# Temperature_and_Altitude.net
KiCad netlist of a schematic drawn in Altium Designer
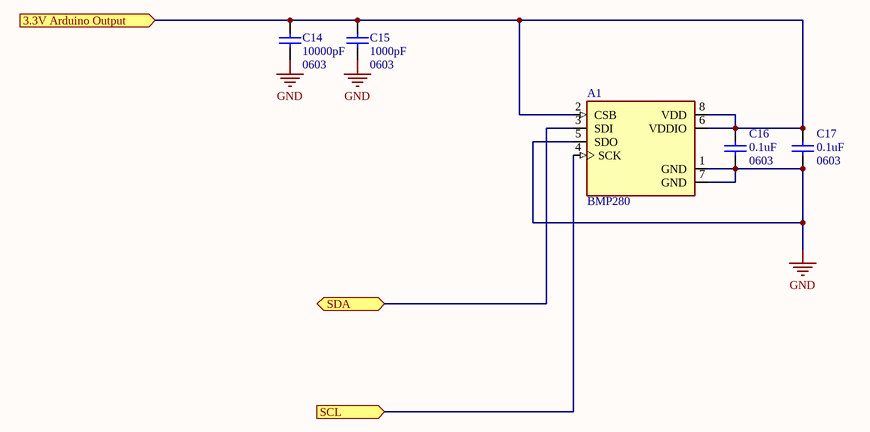
[diagram p0: Temperature and Altitude.SchDoc]

(export (version "E")
  (design (tool "Eeschema 10.0.6"))
  (components
    (comp (ref "A1")
      (value "BMP280")
      (footprint "8-PIN-METAL-LID-LGA")
      (description "Pressure Sensor 4.35PSI ~ 15.95PSI _30kPa ~ 110kPa_ Absolute 16b 8-SMD")
      (fields (field (name "DIGI-KEY_PART_NUMBER") "828-1064-1-ND") (field (name "MF") "Bosch"))
      (libsource (lib "BMP280") (part "BMP280"))
    )
    (comp (ref "C14")
      (value "10000pF")
      (footprint "SMD-0603C")
      (description "Capacitor")
      (fields (field (name "ALTIUM_VALUE") "0603") (field (name "PUBLISHER") "Altium Limited"))
      (libsource (lib "Miscellaneous Devices") (part "Cap"))
    )
    (comp (ref "C15")
      (value "1000pF")
      (footprint "SMD-0603C")
      (description "Capacitor")
      (fields (field (name "ALTIUM_VALUE") "0603") (field (name "PUBLISHER") "Altium Limited"))
      (libsource (lib "Miscellaneous Devices") (part "Cap"))
    )
    (comp (ref "C16")
      (value "0603")
      (footprint "SMD-0603C")
      (description "Capacitor")
      (fields (field (name "ALTIUM_VALUE") "0.1uF") (field (name "PUBLISHER") "Altium Limited"))
      (libsource (lib "Miscellaneous Devices") (part "Cap"))
    )
    (comp (ref "C17")
      (value "0603")
      (footprint "SMD-0603C")
      (description "Capacitor")
      (fields (field (name "ALTIUM_VALUE") "0.1uF") (field (name "PUBLISHER") "Altium Limited"))
      (libsource (lib "Miscellaneous Devices") (part "Cap"))
    )
  )
  (nets
    (net (code "1") (name "/3.3V Arduino Output") (class "Default")
      (node (ref "A1") (pin "2") (pinfunction "CSB_2") (pintype "input"))
      (node (ref "A1") (pin "6") (pinfunction "VDDIO_6") (pintype "power_in"))
      (node (ref "A1") (pin "8") (pinfunction "VDD_8") (pintype "power_in"))
      (node (ref "C14") (pin "2") (pinfunction "2_2") (pintype "passive"))
      (node (ref "C15") (pin "2") (pinfunction "2_2") (pintype "passive"))
      (node (ref "C16") (pin "2") (pinfunction "2_2") (pintype "passive"))
      (node (ref "C17") (pin "2") (pinfunction "2_2") (pintype "passive"))
    )
    (net (code "2") (name "/SCL") (class "Default")
      (node (ref "A1") (pin "4") (pinfunction "SCK_4") (pintype "input"))
    )
    (net (code "3") (name "/SDA") (class "Default")
      (node (ref "A1") (pin "3") (pinfunction "SDI_3") (pintype "bidirectional"))
    )
    (net (code "4") (name "GND") (class "Default")
      (node (ref "A1") (pin "1") (pinfunction "GND_1") (pintype "power_in"))
      (node (ref "A1") (pin "5") (pinfunction "SDO_5") (pintype "bidirectional"))
      (node (ref "A1") (pin "7") (pinfunction "GND_7") (pintype "power_in"))
      (node (ref "C14") (pin "1") (pinfunction "1_1") (pintype "passive"))
      (node (ref "C15") (pin "1") (pinfunction "1_1") (pintype "passive"))
      (node (ref "C16") (pin "1") (pinfunction "1_1") (pintype "passive"))
      (node (ref "C17") (pin "1") (pinfunction "1_1") (pintype "passive"))
    )
  )
)
